# 4_bootleg-alps-periferals.net
KiCad netlist of a schematic drawn in Altium Designer
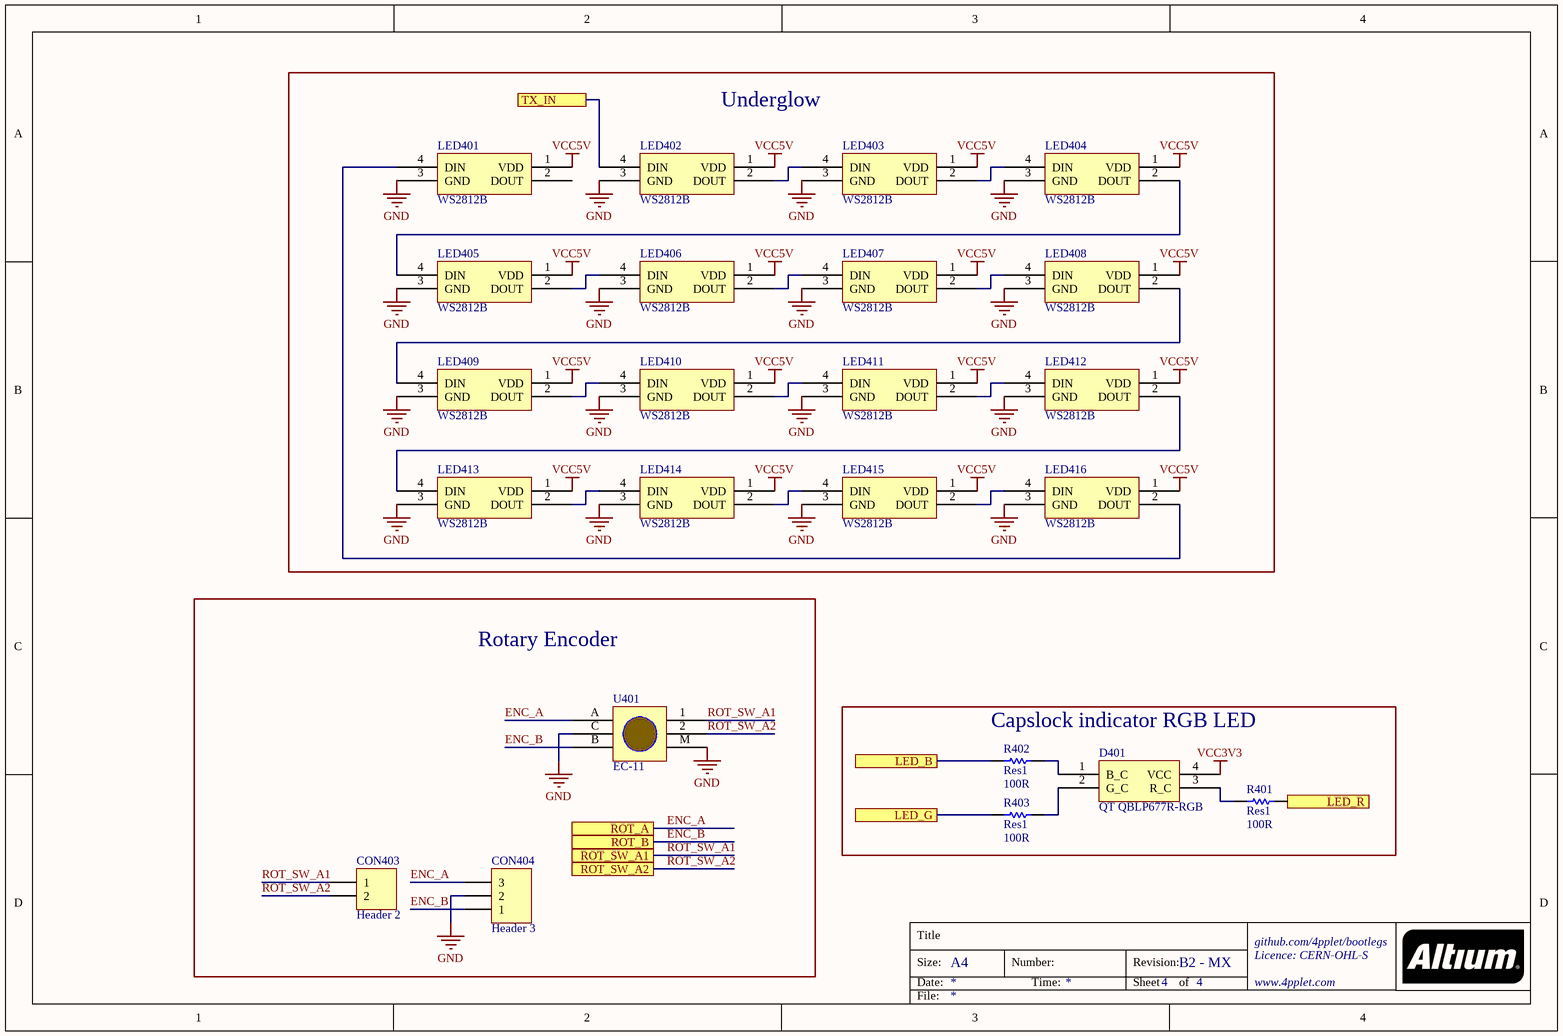
[diagram p0: 4_bootleg-alps-periferals.SchDoc]

(export (version "E")
  (design (tool "Eeschema 10.0.6"))
  (components
    (comp (ref "CON403")
      (value "Header 2")
      (footprint "HDR1X2")
      (description "Header, 2-Pin")
      (libsource (lib "Miscellaneous Connectors") (part "Header 2"))
    )
    (comp (ref "CON404")
      (value "Header 3")
      (footprint "HDR1X3")
      (description "Header, 3-Pin")
      (libsource (lib "Miscellaneous Connectors") (part "Header 3"))
    )
    (comp (ref "D401")
      (value "QT QBLP677R-RGB")
      (footprint "QT QBLP677R-RGB")
      (description "RGB LED")
      (fields (field (name "MFG") "QT Brightek (QTB)"))
      (libsource (lib "Keebs") (part "QT QBLP677R-RGB"))
    )
    (comp (ref "LED401")
      (value "WS2812B")
      (footprint "WS2812B - 2020")
      (fields (field (name "LCSC PART #") "C965555") (field (name "MRF.PART") "WS2812B-2020"))
      (libsource (lib "Keebs") (part "WS2812B"))
    )
    (comp (ref "LED402")
      (value "WS2812B")
      (footprint "WS2812B - 2020")
      (fields (field (name "LCSC PART #") "C965555") (field (name "MRF.PART") "WS2812B-2020"))
      (libsource (lib "Keebs") (part "WS2812B"))
    )
    (comp (ref "LED403")
      (value "WS2812B")
      (footprint "WS2812B - 2020")
      (fields (field (name "LCSC PART #") "C965555") (field (name "MRF.PART") "WS2812B-2020"))
      (libsource (lib "Keebs") (part "WS2812B"))
    )
    (comp (ref "LED404")
      (value "WS2812B")
      (footprint "WS2812B - 2020")
      (fields (field (name "LCSC PART #") "C965555") (field (name "MRF.PART") "WS2812B-2020"))
      (libsource (lib "Keebs") (part "WS2812B"))
    )
    (comp (ref "LED405")
      (value "WS2812B")
      (footprint "WS2812B - 2020")
      (fields (field (name "LCSC PART #") "C965555") (field (name "MRF.PART") "WS2812B-2020"))
      (libsource (lib "Keebs") (part "WS2812B"))
    )
    (comp (ref "LED406")
      (value "WS2812B")
      (footprint "WS2812B - 2020")
      (fields (field (name "LCSC PART #") "C965555") (field (name "MRF.PART") "WS2812B-2020"))
      (libsource (lib "Keebs") (part "WS2812B"))
    )
    (comp (ref "LED407")
      (value "WS2812B")
      (footprint "WS2812B - 2020")
      (fields (field (name "LCSC PART #") "C965555") (field (name "MRF.PART") "WS2812B-2020"))
      (libsource (lib "Keebs") (part "WS2812B"))
    )
    (comp (ref "LED408")
      (value "WS2812B")
      (footprint "WS2812B - 2020")
      (fields (field (name "LCSC PART #") "C965555") (field (name "MRF.PART") "WS2812B-2020"))
      (libsource (lib "Keebs") (part "WS2812B"))
    )
    (comp (ref "LED409")
      (value "WS2812B")
      (footprint "WS2812B - 2020")
      (fields (field (name "LCSC PART #") "C965555") (field (name "MRF.PART") "WS2812B-2020"))
      (libsource (lib "Keebs") (part "WS2812B"))
    )
    (comp (ref "LED410")
      (value "WS2812B")
      (footprint "WS2812B - 2020")
      (fields (field (name "LCSC PART #") "C965555") (field (name "MRF.PART") "WS2812B-2020"))
      (libsource (lib "Keebs") (part "WS2812B"))
    )
    (comp (ref "LED411")
      (value "WS2812B")
      (footprint "WS2812B - 2020")
      (fields (field (name "LCSC PART #") "C965555") (field (name "MRF.PART") "WS2812B-2020"))
      (libsource (lib "Keebs") (part "WS2812B"))
    )
    (comp (ref "LED412")
      (value "WS2812B")
      (footprint "WS2812B - 2020")
      (fields (field (name "LCSC PART #") "C965555") (field (name "MRF.PART") "WS2812B-2020"))
      (libsource (lib "Keebs") (part "WS2812B"))
    )
    (comp (ref "LED413")
      (value "WS2812B")
      (footprint "WS2812B - 2020")
      (fields (field (name "LCSC PART #") "C965555") (field (name "MRF.PART") "WS2812B-2020"))
      (libsource (lib "Keebs") (part "WS2812B"))
    )
    (comp (ref "LED414")
      (value "WS2812B")
      (footprint "WS2812B - 2020")
      (fields (field (name "LCSC PART #") "C965555") (field (name "MRF.PART") "WS2812B-2020"))
      (libsource (lib "Keebs") (part "WS2812B"))
    )
    (comp (ref "LED415")
      (value "WS2812B")
      (footprint "WS2812B - 2020")
      (fields (field (name "LCSC PART #") "C965555") (field (name "MRF.PART") "WS2812B-2020"))
      (libsource (lib "Keebs") (part "WS2812B"))
    )
    (comp (ref "LED416")
      (value "WS2812B")
      (footprint "WS2812B - 2020")
      (fields (field (name "LCSC PART #") "C965555") (field (name "MRF.PART") "WS2812B-2020"))
      (libsource (lib "Keebs") (part "WS2812B"))
    )
    (comp (ref "R401")
      (value "Res1")
      (footprint "R0603[1608]")
      (description "Resistor")
      (fields
        (field (name "ALTIUM_VALUE") "100R")
        (field (name "LCSC PART #") "C22775")
        (field (name "MRF.PART") "0603WAF1000T5E")
      )
      (libsource (lib "Miscellaneous Devices") (part "Res1"))
    )
    (comp (ref "R402")
      (value "Res1")
      (footprint "R0603[1608]")
      (description "Resistor")
      (fields
        (field (name "ALTIUM_VALUE") "100R")
        (field (name "LCSC PART #") "C22775")
        (field (name "MRF.PART") "0603WAF1000T5E")
      )
      (libsource (lib "Miscellaneous Devices") (part "Res1"))
    )
    (comp (ref "R403")
      (value "Res1")
      (footprint "R0603[1608]")
      (description "Resistor")
      (fields
        (field (name "ALTIUM_VALUE") "100R")
        (field (name "LCSC PART #") "C22775")
        (field (name "MRF.PART") "0603WAF1000T5E")
      )
      (libsource (lib "Miscellaneous Devices") (part "Res1"))
    )
    (comp (ref "U401") (value "EC-11") (footprint "EC11-SMD") (libsource (lib "Keebs") (part "EC-11")))
  )
  (nets
    (net (code "1") (name "/ENC_A") (class "Default")
      (node (ref "CON404") (pin "3") (pinfunction "3_3") (pintype "passive"))
      (node (ref "U401") (pin "A") (pinfunction "B_A") (pintype "passive"))
    )
    (net (code "2") (name "/ENC_B") (class "Default")
      (node (ref "CON404") (pin "1") (pinfunction "1_1") (pintype "passive"))
      (node (ref "U401") (pin "B") (pinfunction "B_B") (pintype "passive"))
    )
    (net (code "3") (name "/LED_B") (class "Default")
      (node (ref "R402") (pin "2") (pinfunction "2_2") (pintype "passive"))
    )
    (net (code "4") (name "/LED_G") (class "Default")
      (node (ref "R403") (pin "2") (pinfunction "2_2") (pintype "passive"))
    )
    (net (code "5") (name "/LED_R") (class "Default")
      (node (ref "R401") (pin "1") (pinfunction "1_1") (pintype "passive"))
    )
    (net (code "6") (name "/ROT_SW_A1") (class "Default")
      (node (ref "CON403") (pin "1") (pinfunction "1_1") (pintype "passive"))
      (node (ref "U401") (pin "1") (pinfunction "1_1") (pintype "passive"))
    )
    (net (code "7") (name "/ROT_SW_A2") (class "Default")
      (node (ref "CON403") (pin "2") (pinfunction "2_2") (pintype "passive"))
      (node (ref "U401") (pin "2") (pinfunction "2_2") (pintype "passive"))
    )
    (net (code "8") (name "/TX_IN") (class "Default")
      (node (ref "LED402") (pin "4") (pinfunction "DIN_4") (pintype "passive"))
    )
    (net (code "9") (name "GND") (class "Default")
      (node (ref "CON404") (pin "2") (pinfunction "2_2") (pintype "passive"))
      (node (ref "LED401") (pin "3") (pinfunction "GND_3") (pintype "passive"))
      (node (ref "LED402") (pin "3") (pinfunction "GND_3") (pintype "passive"))
      (node (ref "LED403") (pin "3") (pinfunction "GND_3") (pintype "passive"))
      (node (ref "LED404") (pin "3") (pinfunction "GND_3") (pintype "passive"))
      (node (ref "LED405") (pin "3") (pinfunction "GND_3") (pintype "passive"))
      (node (ref "LED406") (pin "3") (pinfunction "GND_3") (pintype "passive"))
      (node (ref "LED407") (pin "3") (pinfunction "GND_3") (pintype "passive"))
      (node (ref "LED408") (pin "3") (pinfunction "GND_3") (pintype "passive"))
      (node (ref "LED409") (pin "3") (pinfunction "GND_3") (pintype "passive"))
      (node (ref "LED410") (pin "3") (pinfunction "GND_3") (pintype "passive"))
      (node (ref "LED411") (pin "3") (pinfunction "GND_3") (pintype "passive"))
      (node (ref "LED412") (pin "3") (pinfunction "GND_3") (pintype "passive"))
      (node (ref "LED413") (pin "3") (pinfunction "GND_3") (pintype "passive"))
      (node (ref "LED414") (pin "3") (pinfunction "GND_3") (pintype "passive"))
      (node (ref "LED415") (pin "3") (pinfunction "GND_3") (pintype "passive"))
      (node (ref "LED416") (pin "3") (pinfunction "GND_3") (pintype "passive"))
      (node (ref "U401") (pin "C") (pinfunction "C_C") (pintype "passive"))
      (node (ref "U401") (pin "M") (pinfunction "M_M") (pintype "passive"))
    )
    (net (code "10") (name "Net-(D401-B_C)") (class "Default")
      (node (ref "D401") (pin "1") (pinfunction "B_C_1") (pintype "passive"))
      (node (ref "R402") (pin "1") (pinfunction "1_1") (pintype "passive"))
    )
    (net (code "11") (name "Net-(D401-G_C)") (class "Default")
      (node (ref "D401") (pin "2") (pinfunction "G_C_2") (pintype "passive"))
      (node (ref "R403") (pin "1") (pinfunction "1_1") (pintype "passive"))
    )
    (net (code "12") (name "Net-(D401-R_C)") (class "Default")
      (node (ref "D401") (pin "3") (pinfunction "R_C_3") (pintype "passive"))
      (node (ref "R401") (pin "2") (pinfunction "2_2") (pintype "passive"))
    )
    (net (code "13") (name "Net-(LED401-DIN)") (class "Default")
      (node (ref "LED401") (pin "4") (pinfunction "DIN_4") (pintype "passive"))
      (node (ref "LED416") (pin "2") (pinfunction "DOUT_2") (pintype "passive"))
    )
    (net (code "14") (name "Net-(LED402-DOUT)") (class "Default")
      (node (ref "LED402") (pin "2") (pinfunction "DOUT_2") (pintype "passive"))
      (node (ref "LED403") (pin "4") (pinfunction "DIN_4") (pintype "passive"))
    )
    (net (code "15") (name "Net-(LED403-DOUT)") (class "Default")
      (node (ref "LED403") (pin "2") (pinfunction "DOUT_2") (pintype "passive"))
      (node (ref "LED404") (pin "4") (pinfunction "DIN_4") (pintype "passive"))
    )
    (net (code "16") (name "Net-(LED404-DOUT)") (class "Default")
      (node (ref "LED404") (pin "2") (pinfunction "DOUT_2") (pintype "passive"))
      (node (ref "LED405") (pin "4") (pinfunction "DIN_4") (pintype "passive"))
    )
    (net (code "17") (name "Net-(LED405-DOUT)") (class "Default")
      (node (ref "LED405") (pin "2") (pinfunction "DOUT_2") (pintype "passive"))
      (node (ref "LED406") (pin "4") (pinfunction "DIN_4") (pintype "passive"))
    )
    (net (code "18") (name "Net-(LED406-DOUT)") (class "Default")
      (node (ref "LED406") (pin "2") (pinfunction "DOUT_2") (pintype "passive"))
      (node (ref "LED407") (pin "4") (pinfunction "DIN_4") (pintype "passive"))
    )
    (net (code "19") (name "Net-(LED407-DOUT)") (class "Default")
      (node (ref "LED407") (pin "2") (pinfunction "DOUT_2") (pintype "passive"))
      (node (ref "LED408") (pin "4") (pinfunction "DIN_4") (pintype "passive"))
    )
    (net (code "20") (name "Net-(LED408-DOUT)") (class "Default")
      (node (ref "LED408") (pin "2") (pinfunction "DOUT_2") (pintype "passive"))
      (node (ref "LED409") (pin "4") (pinfunction "DIN_4") (pintype "passive"))
    )
    (net (code "21") (name "Net-(LED409-DOUT)") (class "Default")
      (node (ref "LED409") (pin "2") (pinfunction "DOUT_2") (pintype "passive"))
      (node (ref "LED410") (pin "4") (pinfunction "DIN_4") (pintype "passive"))
    )
    (net (code "22") (name "Net-(LED410-DOUT)") (class "Default")
      (node (ref "LED410") (pin "2") (pinfunction "DOUT_2") (pintype "passive"))
      (node (ref "LED411") (pin "4") (pinfunction "DIN_4") (pintype "passive"))
    )
    (net (code "23") (name "Net-(LED411-DOUT)") (class "Default")
      (node (ref "LED411") (pin "2") (pinfunction "DOUT_2") (pintype "passive"))
      (node (ref "LED412") (pin "4") (pinfunction "DIN_4") (pintype "passive"))
    )
    (net (code "24") (name "Net-(LED412-DOUT)") (class "Default")
      (node (ref "LED412") (pin "2") (pinfunction "DOUT_2") (pintype "passive"))
      (node (ref "LED413") (pin "4") (pinfunction "DIN_4") (pintype "passive"))
    )
    (net (code "25") (name "Net-(LED413-DOUT)") (class "Default")
      (node (ref "LED413") (pin "2") (pinfunction "DOUT_2") (pintype "passive"))
      (node (ref "LED414") (pin "4") (pinfunction "DIN_4") (pintype "passive"))
    )
    (net (code "26") (name "Net-(LED414-DOUT)") (class "Default")
      (node (ref "LED414") (pin "2") (pinfunction "DOUT_2") (pintype "passive"))
      (node (ref "LED415") (pin "4") (pinfunction "DIN_4") (pintype "passive"))
    )
    (net (code "27") (name "Net-(LED415-DOUT)") (class "Default")
      (node (ref "LED415") (pin "2") (pinfunction "DOUT_2") (pintype "passive"))
      (node (ref "LED416") (pin "4") (pinfunction "DIN_4") (pintype "passive"))
    )
    (net (code "28") (name "VCC3V3") (class "Default")
      (node (ref "D401") (pin "4") (pinfunction "VCC_4") (pintype "passive"))
    )
    (net (code "29") (name "VCC5V") (class "Default")
      (node (ref "LED401") (pin "1") (pinfunction "VDD_1") (pintype "passive"))
      (node (ref "LED402") (pin "1") (pinfunction "VDD_1") (pintype "passive"))
      (node (ref "LED403") (pin "1") (pinfunction "VDD_1") (pintype "passive"))
      (node (ref "LED404") (pin "1") (pinfunction "VDD_1") (pintype "passive"))
      (node (ref "LED405") (pin "1") (pinfunction "VDD_1") (pintype "passive"))
      (node (ref "LED406") (pin "1") (pinfunction "VDD_1") (pintype "passive"))
      (node (ref "LED407") (pin "1") (pinfunction "VDD_1") (pintype "passive"))
      (node (ref "LED408") (pin "1") (pinfunction "VDD_1") (pintype "passive"))
      (node (ref "LED409") (pin "1") (pinfunction "VDD_1") (pintype "passive"))
      (node (ref "LED410") (pin "1") (pinfunction "VDD_1") (pintype "passive"))
      (node (ref "LED411") (pin "1") (pinfunction "VDD_1") (pintype "passive"))
      (node (ref "LED412") (pin "1") (pinfunction "VDD_1") (pintype "passive"))
      (node (ref "LED413") (pin "1") (pinfunction "VDD_1") (pintype "passive"))
      (node (ref "LED414") (pin "1") (pinfunction "VDD_1") (pintype "passive"))
      (node (ref "LED415") (pin "1") (pinfunction "VDD_1") (pintype "passive"))
      (node (ref "LED416") (pin "1") (pinfunction "VDD_1") (pintype "passive"))
    )
    (net (code "30") (name "unconnected-(LED401-DOUT-Pad2)") (class "Default")
      (node (ref "LED401") (pin "2") (pinfunction "DOUT_2") (pintype "passive"))
    )
  )
)
